# 01_TRANSDUCERS.net
KiCad netlist of a schematic drawn in Altium Designer
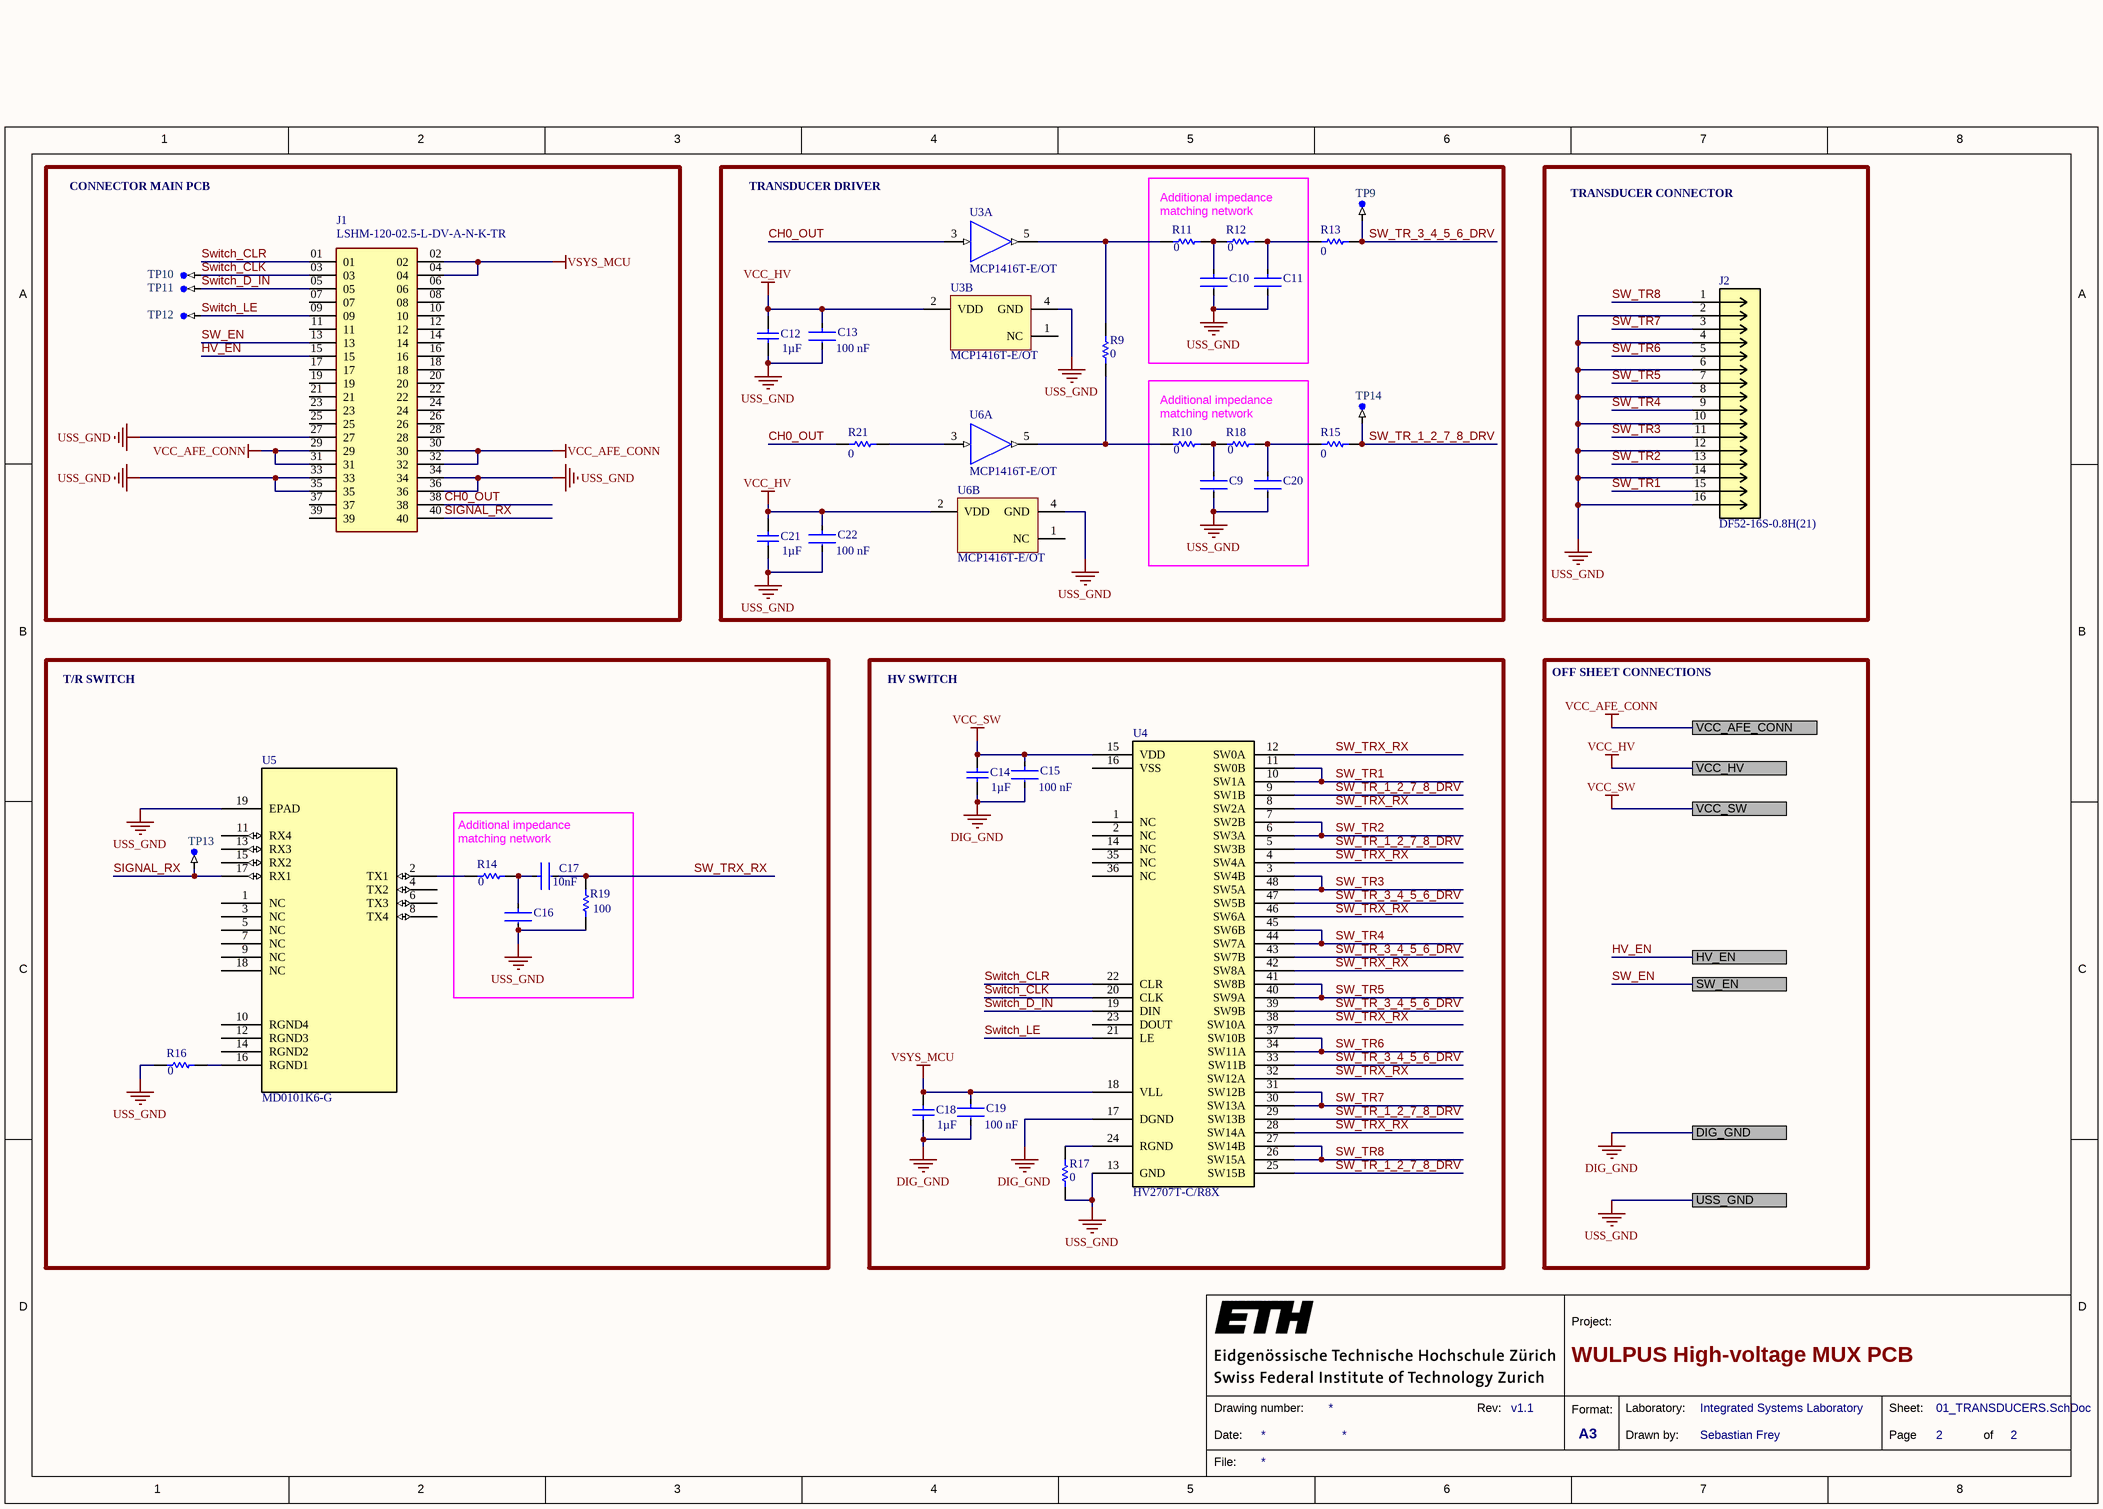
[diagram p0: 01_TRANSDUCERS.SchDoc]

(export (version "E")
  (design (tool "Eeschema 10.0.6"))
  (components
    (comp (ref "C9")
      (value "CC0603KRX7R9BB104")
      (footprint "FP-CC0603-DA-MFG")
      (description "CAP CER 0.1UF 50V X7R 0603")
      (fields (field (name "MANUFACTURER") "YAGEO") (field (name "VOLTAGE") "50 V"))
      (libsource (lib "Altium Content Vault") (part "11868f565c42a9108669ba33697ecf6"))
    )
    (comp (ref "C10")
      (value "CC0603KRX7R9BB104")
      (footprint "FP-CC0603-DA-MFG")
      (description "CAP CER 0.1UF 50V X7R 0603")
      (fields (field (name "MANUFACTURER") "YAGEO") (field (name "VOLTAGE") "50 V"))
      (libsource (lib "Altium Content Vault") (part "11868f565c42a9108669ba33697ecf6"))
    )
    (comp (ref "C11")
      (value "CC0603KRX7R9BB104")
      (footprint "FP-CC0603-DA-MFG")
      (description "CAP CER 0.1UF 50V X7R 0603")
      (fields (field (name "MANUFACTURER") "YAGEO") (field (name "VOLTAGE") "50 V"))
      (libsource (lib "Altium Content Vault") (part "11868f565c42a9108669ba33697ecf6"))
    )
    (comp (ref "C12")
      (value "C1608X5R1H105K080AB")
      (footprint "CAPC1608X90X20LL10")
      (description "Chip Capacitor, 1 uF, +/- 10%, 50 V, -55 to 85 degC, 0603 (1608 Metric), RoHS, Tape and Reel")
      (fields
        (field (name "MANUFACTURER") "TDK")
        (field (name "PCN PART NUMBER") "MLCCPartNumberChange30/Nov/2012")
        (field (name "CAPACITANCE") "1µF")
      )
      (libsource (lib "Altium Content Vault") (part "CAP-NP-2"))
    )
    (comp (ref "C13")
      (value "CC0603KRX7R9BB104")
      (footprint "FP-CC0603-DA-MFG")
      (description "CAP CER 0.1UF 50V X7R 0603")
      (fields
        (field (name "MANUFACTURER") "YAGEO")
        (field (name "VOLTAGE") "50 V")
        (field (name "CAPACITANCE") "100 nF")
      )
      (libsource (lib "Altium Content Vault") (part "11868f565c42a9108669ba33697ecf6"))
    )
    (comp (ref "C14")
      (value "C1608X5R1H105K080AB")
      (footprint "CAPC1608X90X20LL10")
      (description "Chip Capacitor, 1 uF, +/- 10%, 50 V, -55 to 85 degC, 0603 (1608 Metric), RoHS, Tape and Reel")
      (fields
        (field (name "MANUFACTURER") "TDK")
        (field (name "PCN PART NUMBER") "MLCCPartNumberChange30/Nov/2012")
        (field (name "CAPACITANCE") "1µF")
      )
      (libsource (lib "Altium Content Vault") (part "CAP-NP-2"))
    )
    (comp (ref "C15")
      (value "CC0603KRX7R9BB104")
      (footprint "FP-CC0603-DA-MFG")
      (description "CAP CER 0.1UF 50V X7R 0603")
      (fields
        (field (name "MANUFACTURER") "YAGEO")
        (field (name "VOLTAGE") "50 V")
        (field (name "CAPACITANCE") "100 nF")
      )
      (libsource (lib "Altium Content Vault") (part "11868f565c42a9108669ba33697ecf6"))
    )
    (comp (ref "C16")
      (value "CC0603KRX7R9BB104")
      (footprint "FP-CC0603-DA-MFG")
      (description "CAP CER 0.1UF 50V X7R 0603")
      (fields (field (name "MANUFACTURER") "YAGEO") (field (name "VOLTAGE") "50 V"))
      (libsource (lib "Altium Content Vault") (part "11868f565c42a9108669ba33697ecf6"))
    )
    (comp (ref "C17")
      (value "CL05B103KB5NNNC")
      (footprint "FP-CL165-IPC_C")
      (description "Cap Ceramic 10nF 50V X7R ±10% SMD 0402 +125°C Paper T/R")
      (fields
        (field (name "VOLTAGE") "50V")
        (field (name "TOLERANCE") "10%")
        (field (name "CAPACITANCE") "10nF")
      )
      (libsource (lib "Altium Content Vault") (part "b4654b650e69147ec39a6b967a45e02"))
    )
    (comp (ref "C18")
      (value "C1608X5R1H105K080AB")
      (footprint "CAPC1608X90X20LL10")
      (description "Chip Capacitor, 1 uF, +/- 10%, 50 V, -55 to 85 degC, 0603 (1608 Metric), RoHS, Tape and Reel")
      (fields
        (field (name "MANUFACTURER") "TDK")
        (field (name "PCN PART NUMBER") "MLCCPartNumberChange30/Nov/2012")
        (field (name "CAPACITANCE") "1µF")
      )
      (libsource (lib "Altium Content Vault") (part "CAP-NP-2"))
    )
    (comp (ref "C19")
      (value "CC0603KRX7R9BB104")
      (footprint "FP-CC0603-DA-MFG")
      (description "CAP CER 0.1UF 50V X7R 0603")
      (fields
        (field (name "MANUFACTURER") "YAGEO")
        (field (name "VOLTAGE") "50 V")
        (field (name "CAPACITANCE") "100 nF")
      )
      (libsource (lib "Altium Content Vault") (part "11868f565c42a9108669ba33697ecf6"))
    )
    (comp (ref "C20")
      (value "CC0603KRX7R9BB104")
      (footprint "FP-CC0603-DA-MFG")
      (description "CAP CER 0.1UF 50V X7R 0603")
      (fields (field (name "MANUFACTURER") "YAGEO") (field (name "VOLTAGE") "50 V"))
      (libsource (lib "Altium Content Vault") (part "11868f565c42a9108669ba33697ecf6"))
    )
    (comp (ref "C21")
      (value "C1608X5R1H105K080AB")
      (footprint "CAPC1608X90X20LL10")
      (description "Chip Capacitor, 1 uF, +/- 10%, 50 V, -55 to 85 degC, 0603 (1608 Metric), RoHS, Tape and Reel")
      (fields
        (field (name "MANUFACTURER") "TDK")
        (field (name "PCN PART NUMBER") "MLCCPartNumberChange30/Nov/2012")
        (field (name "CAPACITANCE") "1µF")
      )
      (libsource (lib "Altium Content Vault") (part "CAP-NP-2"))
    )
    (comp (ref "C22")
      (value "CC0603KRX7R9BB104")
      (footprint "FP-CC0603-DA-MFG")
      (description "CAP CER 0.1UF 50V X7R 0603")
      (fields
        (field (name "MANUFACTURER") "YAGEO")
        (field (name "VOLTAGE") "50 V")
        (field (name "CAPACITANCE") "100 nF")
      )
      (libsource (lib "Altium Content Vault") (part "11868f565c42a9108669ba33697ecf6"))
    )
    (comp (ref "J1")
      (value "LSHM-120-02.5-L-DV-A-N-K-TR")
      (footprint "PcbLib1:SAMTEC_LSHM-120-XX.X-X-DV-A-N-XX")
      (description "Conn Socket and Terminal Strip HDR/SKT 40 POS 0.5mm Solder ST SMD T/R")
      (fields
        (field (name "MANUFACTURER") "Samtec")
        (field (name "MANUFACTURER PART NUMBER") "LSHM-120-02.5-L-DV-A-N-K-TR")
      )
      (libsource (lib "Schlib1") (part "LSHM-120-02.5-L-DV-A-N-K-TR"))
    )
    (comp (ref "J2")
      (value "DF52-16S-0.8H(21)")
      (footprint "PcbLib1:CONN_DF52-16S-0.8H(21)_HIR")
      (description "No Description Available")
      (fields (field (name "COPYRIGHT") "Copyright (C) 2022 Ultra Librarian. All rights reserved."))
      (libsource (lib "Schlib1") (part "DF52-16S-0.8H(21)"))
    )
    (comp (ref "R9")
      (value "RC0402JR-070RL")
      (footprint "RESC1005X40X25NL05T10")
      (fields (field (name "MANUFACTURER") "Yageo / Phycomp") (field (name "RESISTANCE") "0"))
      (libsource (lib "Altium Content Vault") (part "RES"))
    )
    (comp (ref "R10")
      (value "RC0402JR-070RL")
      (footprint "RESC1005X40X25NL05T10")
      (fields (field (name "MANUFACTURER") "Yageo / Phycomp") (field (name "RESISTANCE") "0"))
      (libsource (lib "Altium Content Vault") (part "RES"))
    )
    (comp (ref "R11")
      (value "RC0402JR-070RL")
      (footprint "RESC1005X40X25NL05T10")
      (fields (field (name "MANUFACTURER") "Yageo / Phycomp") (field (name "RESISTANCE") "0"))
      (libsource (lib "Altium Content Vault") (part "RES"))
    )
    (comp (ref "R12")
      (value "RC0402JR-070RL")
      (footprint "RESC1005X40X25NL05T10")
      (fields (field (name "MANUFACTURER") "Yageo / Phycomp") (field (name "RESISTANCE") "0"))
      (libsource (lib "Altium Content Vault") (part "RES"))
    )
    (comp (ref "R13")
      (value "RC0402JR-070RL")
      (footprint "RESC1005X40X25NL05T10")
      (fields (field (name "MANUFACTURER") "Yageo / Phycomp") (field (name "RESISTANCE") "0"))
      (libsource (lib "Altium Content Vault") (part "RES"))
    )
    (comp (ref "R14")
      (value "RC0402JR-070RL")
      (footprint "RESC1005X40X25NL05T10")
      (fields (field (name "MANUFACTURER") "Yageo / Phycomp") (field (name "RESISTANCE") "0"))
      (libsource (lib "Altium Content Vault") (part "RES"))
    )
    (comp (ref "R15")
      (value "RC0402JR-070RL")
      (footprint "RESC1005X40X25NL05T10")
      (fields (field (name "MANUFACTURER") "Yageo / Phycomp") (field (name "RESISTANCE") "0"))
      (libsource (lib "Altium Content Vault") (part "RES"))
    )
    (comp (ref "R16")
      (value "RC0402JR-070RL")
      (footprint "RESC1005X40X25NL05T10")
      (fields (field (name "MANUFACTURER") "Yageo / Phycomp") (field (name "RESISTANCE") "0"))
      (libsource (lib "Altium Content Vault") (part "RES"))
    )
    (comp (ref "R17")
      (value "RC0402JR-070RL")
      (footprint "RESC1005X40X25NL05T10")
      (fields (field (name "MANUFACTURER") "Yageo / Phycomp") (field (name "RESISTANCE") "0"))
      (libsource (lib "Altium Content Vault") (part "RES"))
    )
    (comp (ref "R18")
      (value "RC0402JR-070RL")
      (footprint "RESC1005X40X25NL05T10")
      (fields (field (name "MANUFACTURER") "Yageo / Phycomp") (field (name "RESISTANCE") "0"))
      (libsource (lib "Altium Content Vault") (part "RES"))
    )
    (comp (ref "R19")
      (value "ERJ-2GEJ101X")
      (footprint "RESC1005X40X25NL05T05")
      (fields (field (name "MANUFACTURER") "Panasonic") (field (name "RESISTANCE") "100"))
      (libsource (lib "Altium Content Vault") (part "RES"))
    )
    (comp (ref "R21")
      (value "RC0402JR-070RL")
      (footprint "RESC1005X40X25NL05T10")
      (fields (field (name "MANUFACTURER") "Yageo / Phycomp") (field (name "RESISTANCE") "0"))
      (libsource (lib "Altium Content Vault") (part "RES"))
    )
    (comp (ref "TP9")
      (value "TP-SM-C-100")
      (footprint "TP-SM-C-100")
      (description "Test Point, Surface Mount, Circular, Pad Diameter 1 mm")
      (libsource (lib "Altium Content Vault") (part "TP-SM"))
    )
    (comp (ref "TP10")
      (value "TP-SM-C-100")
      (footprint "TP-SM-C-100")
      (description "Test Point, Surface Mount, Circular, Pad Diameter 1 mm")
      (libsource (lib "Altium Content Vault") (part "TP-SM"))
    )
    (comp (ref "TP11")
      (value "TP-SM-C-100")
      (footprint "TP-SM-C-100")
      (description "Test Point, Surface Mount, Circular, Pad Diameter 1 mm")
      (libsource (lib "Altium Content Vault") (part "TP-SM"))
    )
    (comp (ref "TP12")
      (value "TP-SM-C-100")
      (footprint "TP-SM-C-100")
      (description "Test Point, Surface Mount, Circular, Pad Diameter 1 mm")
      (libsource (lib "Altium Content Vault") (part "TP-SM"))
    )
    (comp (ref "TP13")
      (value "TP-SM-C-100")
      (footprint "TP-SM-C-100")
      (description "Test Point, Surface Mount, Circular, Pad Diameter 1 mm")
      (libsource (lib "Altium Content Vault") (part "TP-SM"))
    )
    (comp (ref "TP14")
      (value "TP-SM-C-100")
      (footprint "TP-SM-C-100")
      (description "Test Point, Surface Mount, Circular, Pad Diameter 1 mm")
      (libsource (lib "Altium Content Vault") (part "TP-SM"))
    )
    (comp (ref "U3")
      (value "MCP1416T-E/OT")
      (footprint "SOT-23-OT5_M")
      (description "Tiny 1.5A, High-Speed Power MOSFET Driver, Non Inverting, Extended Temperature, Tape and Reel")
      (libsource (lib "Altium Content Vault") (part "IN-MOSDRV-MCP1416-5"))
    )
    (comp (ref "U4")
      (value "HV2707T-C/R8X")
      (footprint "PcbLib1:LQFP48_7X7MC_MCH")
      (description "16-CH 200V No Hv Bias Switch (SPST), 2 Bleed Resistor 48 LQFP 7X7X1.4MM T/r Rohs Compliant: Yes")
      (fields
        (field (name "MANUFACTURER") "Microchip")
        (field (name "MANUFACTURER PART NUMBER") "HV2707T-C/R8X")
      )
      (libsource (lib "Schlib1") (part "HV2707T-C/R8X"))
    )
    (comp (ref "U5")
      (value "MD0101K6-G")
      (footprint "PcbLib1:DFN18_5X5_MCH")
      (description "No Description Available")
      (fields (field (name "COPYRIGHT") "Copyright (C) 2022 Ultra Librarian. All rights reserved."))
      (libsource (lib "Schlib1") (part "MD0101K6-G"))
    )
    (comp (ref "U6")
      (value "MCP1416T-E/OT")
      (footprint "SOT-23-OT5_M")
      (description "Tiny 1.5A, High-Speed Power MOSFET Driver, Non Inverting, Extended Temperature, Tape and Reel")
      (libsource (lib "Altium Content Vault") (part "IN-MOSDRV-MCP1416-5"))
    )
  )
  (nets
    (net (code "2") (name "/CH0_OUT") (class "Default")
      (node (ref "J1") (pin "38") (pinfunction "38_38") (pintype "passive"))
      (node (ref "R21") (pin "1") (pinfunction "1_1") (pintype "passive"))
      (node (ref "U3") (pin "3") (pinfunction "IN_3") (pintype "input"))
    )
    (net (code "3") (name "/HV_EN") (class "Default")
      (node (ref "J1") (pin "15") (pinfunction "15_15") (pintype "passive"))
    )
    (net (code "4") (name "/SIGNAL_RX") (class "Default")
      (node (ref "J1") (pin "40") (pinfunction "40_40") (pintype "passive"))
      (node (ref "TP13") (pin "1") (pinfunction "1_1") (pintype "input"))
      (node (ref "U5") (pin "17") (pinfunction "RX1_17") (pintype "bidirectional"))
    )
    (net (code "5") (name "/SW_EN") (class "Default")
      (node (ref "J1") (pin "13") (pinfunction "13_13") (pintype "passive"))
    )
    (net (code "6") (name "/SW_TR1") (class "Default")
      (node (ref "J2") (pin "15") (pinfunction "15_15") (pintype "passive"))
      (node (ref "U4") (pin "10") (pinfunction "SW1A_10") (pintype "passive"))
      (node (ref "U4") (pin "11") (pinfunction "SW0B_11") (pintype "passive"))
    )
    (net (code "7") (name "/SW_TR2") (class "Default")
      (node (ref "J2") (pin "13") (pinfunction "13_13") (pintype "passive"))
      (node (ref "U4") (pin "6") (pinfunction "SW3A_6") (pintype "passive"))
      (node (ref "U4") (pin "7") (pinfunction "SW2B_7") (pintype "passive"))
    )
    (net (code "8") (name "/SW_TR3") (class "Default")
      (node (ref "J2") (pin "11") (pinfunction "11_11") (pintype "passive"))
      (node (ref "U4") (pin "3") (pinfunction "SW4B_3") (pintype "passive"))
      (node (ref "U4") (pin "48") (pinfunction "SW5A_48") (pintype "passive"))
    )
    (net (code "9") (name "/SW_TR4") (class "Default")
      (node (ref "J2") (pin "9") (pinfunction "9_9") (pintype "passive"))
      (node (ref "U4") (pin "44") (pinfunction "SW7A_44") (pintype "passive"))
      (node (ref "U4") (pin "45") (pinfunction "SW6B_45") (pintype "passive"))
    )
    (net (code "10") (name "/SW_TR5") (class "Default")
      (node (ref "J2") (pin "7") (pinfunction "7_7") (pintype "passive"))
      (node (ref "U4") (pin "40") (pinfunction "SW9A_40") (pintype "passive"))
      (node (ref "U4") (pin "41") (pinfunction "SW8B_41") (pintype "passive"))
    )
    (net (code "11") (name "/SW_TR6") (class "Default")
      (node (ref "J2") (pin "5") (pinfunction "5_5") (pintype "passive"))
      (node (ref "U4") (pin "34") (pinfunction "SW11A_34") (pintype "passive"))
      (node (ref "U4") (pin "37") (pinfunction "SW10B_37") (pintype "passive"))
    )
    (net (code "12") (name "/SW_TR7") (class "Default")
      (node (ref "J2") (pin "3") (pinfunction "3_3") (pintype "passive"))
      (node (ref "U4") (pin "30") (pinfunction "SW13A_30") (pintype "passive"))
      (node (ref "U4") (pin "31") (pinfunction "SW12B_31") (pintype "passive"))
    )
    (net (code "13") (name "/SW_TR8") (class "Default")
      (node (ref "J2") (pin "1") (pinfunction "1_1") (pintype "passive"))
      (node (ref "U4") (pin "26") (pinfunction "SW15A_26") (pintype "passive"))
      (node (ref "U4") (pin "27") (pinfunction "SW14B_27") (pintype "passive"))
    )
    (net (code "14") (name "/SW_TRX_RX") (class "Default")
      (node (ref "C17") (pin "2") (pinfunction "2_2") (pintype "passive"))
      (node (ref "R19") (pin "2") (pinfunction "2_2") (pintype "passive"))
      (node (ref "U4") (pin "12") (pinfunction "SW0A_12") (pintype "passive"))
      (node (ref "U4") (pin "28") (pinfunction "SW14A_28") (pintype "passive"))
      (node (ref "U4") (pin "32") (pinfunction "SW12A_32") (pintype "passive"))
      (node (ref "U4") (pin "38") (pinfunction "SW10A_38") (pintype "passive"))
      (node (ref "U4") (pin "4") (pinfunction "SW4A_4") (pintype "passive"))
      (node (ref "U4") (pin "42") (pinfunction "SW8A_42") (pintype "passive"))
      (node (ref "U4") (pin "46") (pinfunction "SW6A_46") (pintype "passive"))
      (node (ref "U4") (pin "8") (pinfunction "SW2A_8") (pintype "passive"))
    )
    (net (code "15") (name "/SW_TR_1_2_7_8_DRV") (class "Default")
      (node (ref "R15") (pin "2") (pinfunction "2_2") (pintype "passive"))
      (node (ref "TP14") (pin "1") (pinfunction "1_1") (pintype "input"))
      (node (ref "U4") (pin "25") (pinfunction "SW15B_25") (pintype "passive"))
      (node (ref "U4") (pin "29") (pinfunction "SW13B_29") (pintype "passive"))
      (node (ref "U4") (pin "5") (pinfunction "SW3B_5") (pintype "passive"))
      (node (ref "U4") (pin "9") (pinfunction "SW1B_9") (pintype "passive"))
    )
    (net (code "16") (name "/SW_TR_3_4_5_6_DRV") (class "Default")
      (node (ref "R13") (pin "2") (pinfunction "2_2") (pintype "passive"))
      (node (ref "TP9") (pin "1") (pinfunction "1_1") (pintype "input"))
      (node (ref "U4") (pin "33") (pinfunction "SW11B_33") (pintype "passive"))
      (node (ref "U4") (pin "39") (pinfunction "SW9B_39") (pintype "passive"))
      (node (ref "U4") (pin "43") (pinfunction "SW7B_43") (pintype "passive"))
      (node (ref "U4") (pin "47") (pinfunction "SW5B_47") (pintype "passive"))
    )
    (net (code "17") (name "/Switch_CLK") (class "Default")
      (node (ref "J1") (pin "03") (pinfunction "03_03") (pintype "passive"))
      (node (ref "TP10") (pin "1") (pinfunction "1_1") (pintype "input"))
      (node (ref "U4") (pin "20") (pinfunction "CLK_20") (pintype "passive"))
    )
    (net (code "18") (name "/Switch_CLR") (class "Default")
      (node (ref "J1") (pin "01") (pinfunction "01_01") (pintype "passive"))
      (node (ref "U4") (pin "22") (pinfunction "CLR_22") (pintype "passive"))
    )
    (net (code "19") (name "/Switch_D_IN") (class "Default")
      (node (ref "J1") (pin "05") (pinfunction "05_05") (pintype "passive"))
      (node (ref "TP11") (pin "1") (pinfunction "1_1") (pintype "input"))
      (node (ref "U4") (pin "19") (pinfunction "DIN_19") (pintype "passive"))
    )
    (net (code "20") (name "/Switch_LE") (class "Default")
      (node (ref "J1") (pin "09") (pinfunction "09_09") (pintype "passive"))
      (node (ref "TP12") (pin "1") (pinfunction "1_1") (pintype "input"))
      (node (ref "U4") (pin "21") (pinfunction "LE_21") (pintype "passive"))
    )
    (net (code "21") (name "DIG_GND") (class "Default")
      (node (ref "C14") (pin "1") (pinfunction "1_1") (pintype "passive"))
      (node (ref "C15") (pin "2") (pinfunction "2_2") (pintype "passive"))
      (node (ref "C18") (pin "1") (pinfunction "1_1") (pintype "passive"))
      (node (ref "C19") (pin "2") (pinfunction "2_2") (pintype "passive"))
      (node (ref "U4") (pin "17") (pinfunction "DGND_17") (pintype "passive"))
    )
    (net (code "22") (name "Net-(C9-Pad1)") (class "Default")
      (node (ref "C9") (pin "1") (pinfunction "1_1") (pintype "passive"))
      (node (ref "R10") (pin "1") (pinfunction "1_1") (pintype "passive"))
      (node (ref "R18") (pin "2") (pinfunction "2_2") (pintype "passive"))
    )
    (net (code "23") (name "Net-(C10-Pad1)") (class "Default")
      (node (ref "C10") (pin "1") (pinfunction "1_1") (pintype "passive"))
      (node (ref "R11") (pin "1") (pinfunction "1_1") (pintype "passive"))
      (node (ref "R12") (pin "2") (pinfunction "2_2") (pintype "passive"))
    )
    (net (code "24") (name "Net-(C11-Pad1)") (class "Default")
      (node (ref "C11") (pin "1") (pinfunction "1_1") (pintype "passive"))
      (node (ref "R12") (pin "1") (pinfunction "1_1") (pintype "passive"))
      (node (ref "R13") (pin "1") (pinfunction "1_1") (pintype "passive"))
    )
    (net (code "25") (name "Net-(C16-Pad1)") (class "Default")
      (node (ref "C16") (pin "1") (pinfunction "1_1") (pintype "passive"))
      (node (ref "C17") (pin "1") (pinfunction "1_1") (pintype "passive"))
      (node (ref "R14") (pin "1") (pinfunction "1_1") (pintype "passive"))
    )
    (net (code "26") (name "Net-(C20-Pad1)") (class "Default")
      (node (ref "C20") (pin "1") (pinfunction "1_1") (pintype "passive"))
      (node (ref "R15") (pin "1") (pinfunction "1_1") (pintype "passive"))
      (node (ref "R18") (pin "1") (pinfunction "1_1") (pintype "passive"))
    )
    (net (code "27") (name "Net-(U3A-OUT)") (class "Default")
      (node (ref "R11") (pin "2") (pinfunction "2_2") (pintype "passive"))
      (node (ref "R9") (pin "1") (pinfunction "1_1") (pintype "passive"))
      (node (ref "U3") (pin "5") (pinfunction "OUT_5") (pintype "output"))
    )
    (net (code "28") (name "Net-(U4-RGND)") (class "Default")
      (node (ref "R17") (pin "1") (pinfunction "1_1") (pintype "passive"))
      (node (ref "U4") (pin "24") (pinfunction "RGND_24") (pintype "passive"))
    )
    (net (code "29") (name "Net-(U5-RGND1)") (class "Default")
      (node (ref "R16") (pin "1") (pinfunction "1_1") (pintype "passive"))
      (node (ref "U5") (pin "16") (pinfunction "RGND1_16") (pintype "passive"))
    )
    (net (code "30") (name "Net-(U5-TX1)") (class "Default")
      (node (ref "R14") (pin "2") (pinfunction "2_2") (pintype "passive"))
      (node (ref "U5") (pin "2") (pinfunction "TX1_2") (pintype "bidirectional"))
    )
    (net (code "31") (name "Net-(U6A-IN)") (class "Default")
      (node (ref "R21") (pin "2") (pinfunction "2_2") (pintype "passive"))
      (node (ref "U6") (pin "3") (pinfunction "IN_3") (pintype "input"))
    )
    (net (code "32") (name "Net-(U6A-OUT)") (class "Default")
      (node (ref "R10") (pin "2") (pinfunction "2_2") (pintype "passive"))
      (node (ref "R9") (pin "2") (pinfunction "2_2") (pintype "passive"))
      (node (ref "U6") (pin "5") (pinfunction "OUT_5") (pintype "output"))
    )
    (net (code "33") (name "USS_GND") (class "Default")
      (node (ref "C10") (pin "2") (pinfunction "2_2") (pintype "passive"))
      (node (ref "C11") (pin "2") (pinfunction "2_2") (pintype "passive"))
      (node (ref "C12") (pin "1") (pinfunction "1_1") (pintype "passive"))
      (node (ref "C13") (pin "2") (pinfunction "2_2") (pintype "passive"))
      (node (ref "C16") (pin "2") (pinfunction "2_2") (pintype "passive"))
      (node (ref "C20") (pin "2") (pinfunction "2_2") (pintype "passive"))
      (node (ref "C21") (pin "1") (pinfunction "1_1") (pintype "passive"))
      (node (ref "C22") (pin "2") (pinfunction "2_2") (pintype "passive"))
      (node (ref "C9") (pin "2") (pinfunction "2_2") (pintype "passive"))
      (node (ref "J1") (pin "27") (pinfunction "27_27") (pintype "passive"))
      (node (ref "J1") (pin "33") (pinfunction "33_33") (pintype "passive"))
      (node (ref "J1") (pin "34") (pinfunction "34_34") (pintype "passive"))
      (node (ref "J1") (pin "35") (pinfunction "35_35") (pintype "passive"))
      (node (ref "J1") (pin "36") (pinfunction "36_36") (pintype "passive"))
      (node (ref "J2") (pin "10") (pinfunction "10_10") (pintype "passive"))
      (node (ref "J2") (pin "12") (pinfunction "12_12") (pintype "passive"))
      (node (ref "J2") (pin "14") (pinfunction "14_14") (pintype "passive"))
      (node (ref "J2") (pin "16") (pinfunction "16_16") (pintype "passive"))
      (node (ref "J2") (pin "2") (pinfunction "2_2") (pintype "passive"))
      (node (ref "J2") (pin "4") (pinfunction "4_4") (pintype "passive"))
      (node (ref "J2") (pin "6") (pinfunction "6_6") (pintype "passive"))
      (node (ref "J2") (pin "8") (pinfunction "8_8") (pintype "passive"))
      (node (ref "R16") (pin "2") (pinfunction "2_2") (pintype "passive"))
      (node (ref "R17") (pin "2") (pinfunction "2_2") (pintype "passive"))
      (node (ref "R19") (pin "1") (pinfunction "1_1") (pintype "passive"))
      (node (ref "U3") (pin "4") (pinfunction "GND_4") (pintype "power_in"))
      (node (ref "U4") (pin "13") (pinfunction "GND_13") (pintype "passive"))
      (node (ref "U5") (pin "19") (pinfunction "EPAD_19") (pintype "passive"))
      (node (ref "U6") (pin "4") (pinfunction "GND_4") (pintype "power_in"))
    )
    (net (code "34") (name "VCC_AFE_CONN") (class "Default")
      (node (ref "J1") (pin "29") (pinfunction "29_29") (pintype "passive"))
      (node (ref "J1") (pin "30") (pinfunction "30_30") (pintype "passive"))
      (node (ref "J1") (pin "31") (pinfunction "31_31") (pintype "passive"))
      (node (ref "J1") (pin "32") (pinfunction "32_32") (pintype "passive"))
    )
    (net (code "35") (name "VCC_HV") (class "Default")
      (node (ref "C12") (pin "2") (pinfunction "2_2") (pintype "passive"))
      (node (ref "C13") (pin "1") (pinfunction "1_1") (pintype "passive"))
      (node (ref "C21") (pin "2") (pinfunction "2_2") (pintype "passive"))
      (node (ref "C22") (pin "1") (pinfunction "1_1") (pintype "passive"))
      (node (ref "U3") (pin "2") (pinfunction "VDD_2") (pintype "power_in"))
      (node (ref "U6") (pin "2") (pinfunction "VDD_2") (pintype "power_in"))
    )
    (net (code "36") (name "VCC_SW") (class "Default")
      (node (ref "C14") (pin "2") (pinfunction "2_2") (pintype "passive"))
      (node (ref "C15") (pin "1") (pinfunction "1_1") (pintype "passive"))
      (node (ref "U4") (pin "15") (pinfunction "VDD_15") (pintype "passive"))
    )
    (net (code "37") (name "VSYS_MCU") (class "Default")
      (node (ref "C18") (pin "2") (pinfunction "2_2") (pintype "passive"))
      (node (ref "C19") (pin "1") (pinfunction "1_1") (pintype "passive"))
      (node (ref "J1") (pin "02") (pinfunction "02_02") (pintype "passive"))
      (node (ref "J1") (pin "04") (pinfunction "04_04") (pintype "passive"))
      (node (ref "U4") (pin "18") (pinfunction "VLL_18") (pintype "passive"))
    )
    (net (code "38") (name "unconnected-(J1-Pad06)") (class "Default")
      (node (ref "J1") (pin "06") (pinfunction "06_06") (pintype "passive"))
    )
    (net (code "39") (name "unconnected-(J1-Pad07)") (class "Default")
      (node (ref "J1") (pin "07") (pinfunction "07_07") (pintype "passive"))
    )
    (net (code "40") (name "unconnected-(J1-Pad08)") (class "Default")
      (node (ref "J1") (pin "08") (pinfunction "08_08") (pintype "passive"))
    )
    (net (code "41") (name "unconnected-(J1-Pad10)") (class "Default")
      (node (ref "J1") (pin "10") (pinfunction "10_10") (pintype "passive"))
    )
    (net (code "42") (name "unconnected-(J1-Pad11)") (class "Default")
      (node (ref "J1") (pin "11") (pinfunction "11_11") (pintype "passive"))
    )
    (net (code "43") (name "unconnected-(J1-Pad12)") (class "Default")
      (node (ref "J1") (pin "12") (pinfunction "12_12") (pintype "passive"))
    )
    (net (code "44") (name "unconnected-(J1-Pad14)") (class "Default")
      (node (ref "J1") (pin "14") (pinfunction "14_14") (pintype "passive"))
    )
    (net (code "45") (name "unconnected-(J1-Pad16)") (class "Default")
      (node (ref "J1") (pin "16") (pinfunction "16_16") (pintype "passive"))
    )
    (net (code "46") (name "unconnected-(J1-Pad17)") (class "Default")
      (node (ref "J1") (pin "17") (pinfunction "17_17") (pintype "passive"))
    )
    (net (code "47") (name "unconnected-(J1-Pad18)") (class "Default")
      (node (ref "J1") (pin "18") (pinfunction "18_18") (pintype "passive"))
    )
    (net (code "48") (name "unconnected-(J1-Pad19)") (class "Default")
      (node (ref "J1") (pin "19") (pinfunction "19_19") (pintype "passive"))
    )
    (net (code "49") (name "unconnected-(J1-Pad20)") (class "Default")
      (node (ref "J1") (pin "20") (pinfunction "20_20") (pintype "passive"))
    )
    (net (code "50") (name "unconnected-(J1-Pad21)") (class "Default")
      (node (ref "J1") (pin "21") (pinfunction "21_21") (pintype "passive"))
    )
    (net (code "51") (name "unconnected-(J1-Pad22)") (class "Default")
      (node (ref "J1") (pin "22") (pinfunction "22_22") (pintype "passive"))
    )
    (net (code "52") (name "unconnected-(J1-Pad23)") (class "Default")
      (node (ref "J1") (pin "23") (pinfunction "23_23") (pintype "passive"))
    )
    (net (code "53") (name "unconnected-(J1-Pad24)") (class "Default")
      (node (ref "J1") (pin "24") (pinfunction "24_24") (pintype "passive"))
    )
    (net (code "54") (name "unconnected-(J1-Pad25)") (class "Default")
      (node (ref "J1") (pin "25") (pinfunction "25_25") (pintype "passive"))
    )
    (net (code "55") (name "unconnected-(J1-Pad26)") (class "Default")
      (node (ref "J1") (pin "26") (pinfunction "26_26") (pintype "passive"))
    )
    (net (code "56") (name "unconnected-(J1-Pad28)") (class "Default")
      (node (ref "J1") (pin "28") (pinfunction "28_28") (pintype "passive"))
    )
    (net (code "57") (name "unconnected-(J1-Pad37)") (class "Default")
      (node (ref "J1") (pin "37") (pinfunction "37_37") (pintype "passive"))
    )
    (net (code "58") (name "unconnected-(J1-Pad39)") (class "Default")
      (node (ref "J1") (pin "39") (pinfunction "39_39") (pintype "passive"))
    )
    (net (code "59") (name "unconnected-(U3B-NC-Pad1)") (class "Default")
      (node (ref "U3") (pin "1") (pinfunction "NC_1") (pintype "passive"))
    )
    (net (code "60") (name "unconnected-(U4-DOUT-Pad23)") (class "Default")
      (node (ref "U4") (pin "23") (pinfunction "DOUT_23") (pintype "passive"))
    )
    (net (code "61") (name "unconnected-(U4-NC-Pad1)") (class "Default")
      (node (ref "U4") (pin "1") (pinfunction "NC_1") (pintype "passive"))
    )
    (net (code "62") (name "unconnected-(U4-NC-Pad2)") (class "Default")
      (node (ref "U4") (pin "2") (pinfunction "NC_2") (pintype "passive"))
    )
    (net (code "63") (name "unconnected-(U4-NC-Pad14)") (class "Default")
      (node (ref "U4") (pin "14") (pinfunction "NC_14") (pintype "passive"))
    )
    (net (code "64") (name "unconnected-(U4-NC-Pad35)") (class "Default")
      (node (ref "U4") (pin "35") (pinfunction "NC_35") (pintype "passive"))
    )
    (net (code "65") (name "unconnected-(U4-NC-Pad36)") (class "Default")
      (node (ref "U4") (pin "36") (pinfunction "NC_36") (pintype "passive"))
    )
    (net (code "66") (name "unconnected-(U4-VSS-Pad16)") (class "Default")
      (node (ref "U4") (pin "16") (pinfunction "VSS_16") (pintype "passive"))
    )
    (net (code "67") (name "unconnected-(U5-NC-Pad1)") (class "Default")
      (node (ref "U5") (pin "1") (pinfunction "NC_1") (pintype "passive"))
    )
    (net (code "68") (name "unconnected-(U5-NC-Pad3)") (class "Default")
      (node (ref "U5") (pin "3") (pinfunction "NC_3") (pintype "passive"))
    )
    (net (code "69") (name "unconnected-(U5-NC-Pad5)") (class "Default")
      (node (ref "U5") (pin "5") (pinfunction "NC_5") (pintype "passive"))
    )
    (net (code "70") (name "unconnected-(U5-NC-Pad7)") (class "Default")
      (node (ref "U5") (pin "7") (pinfunction "NC_7") (pintype "passive"))
    )
    (net (code "71") (name "unconnected-(U5-NC-Pad9)") (class "Default")
      (node (ref "U5") (pin "9") (pinfunction "NC_9") (pintype "passive"))
    )
    (net (code "72") (name "unconnected-(U5-NC-Pad18)") (class "Default")
      (node (ref "U5") (pin "18") (pinfunction "NC_18") (pintype "passive"))
    )
    (net (code "73") (name "unconnected-(U5-RGND2-Pad14)") (class "Default")
      (node (ref "U5") (pin "14") (pinfunction "RGND2_14") (pintype "passive"))
    )
    (net (code "74") (name "unconnected-(U5-RGND3-Pad12)") (class "Default")
      (node (ref "U5") (pin "12") (pinfunction "RGND3_12") (pintype "passive"))
    )
    (net (code "75") (name "unconnected-(U5-RGND4-Pad10)") (class "Default")
      (node (ref "U5") (pin "10") (pinfunction "RGND4_10") (pintype "passive"))
    )
    (net (code "76") (name "unconnected-(U5-RX2-Pad15)") (class "Default")
      (node (ref "U5") (pin "15") (pinfunction "RX2_15") (pintype "bidirectional"))
    )
    (net (code "77") (name "unconnected-(U5-RX3-Pad13)") (class "Default")
      (node (ref "U5") (pin "13") (pinfunction "RX3_13") (pintype "bidirectional"))
    )
    (net (code "78") (name "unconnected-(U5-RX4-Pad11)") (class "Default")
      (node (ref "U5") (pin "11") (pinfunction "RX4_11") (pintype "bidirectional"))
    )
    (net (code "79") (name "unconnected-(U5-TX2-Pad4)") (class "Default")
      (node (ref "U5") (pin "4") (pinfunction "TX2_4") (pintype "bidirectional"))
    )
    (net (code "80") (name "unconnected-(U5-TX3-Pad6)") (class "Default")
      (node (ref "U5") (pin "6") (pinfunction "TX3_6") (pintype "bidirectional"))
    )
    (net (code "81") (name "unconnected-(U5-TX4-Pad8)") (class "Default")
      (node (ref "U5") (pin "8") (pinfunction "TX4_8") (pintype "bidirectional"))
    )
    (net (code "82") (name "unconnected-(U6B-NC-Pad1)") (class "Default")
      (node (ref "U6") (pin "1") (pinfunction "NC_1") (pintype "passive"))
    )
  )
)
